# jan_ray2.net
KiCad netlist of a schematic drawn in EAGLE
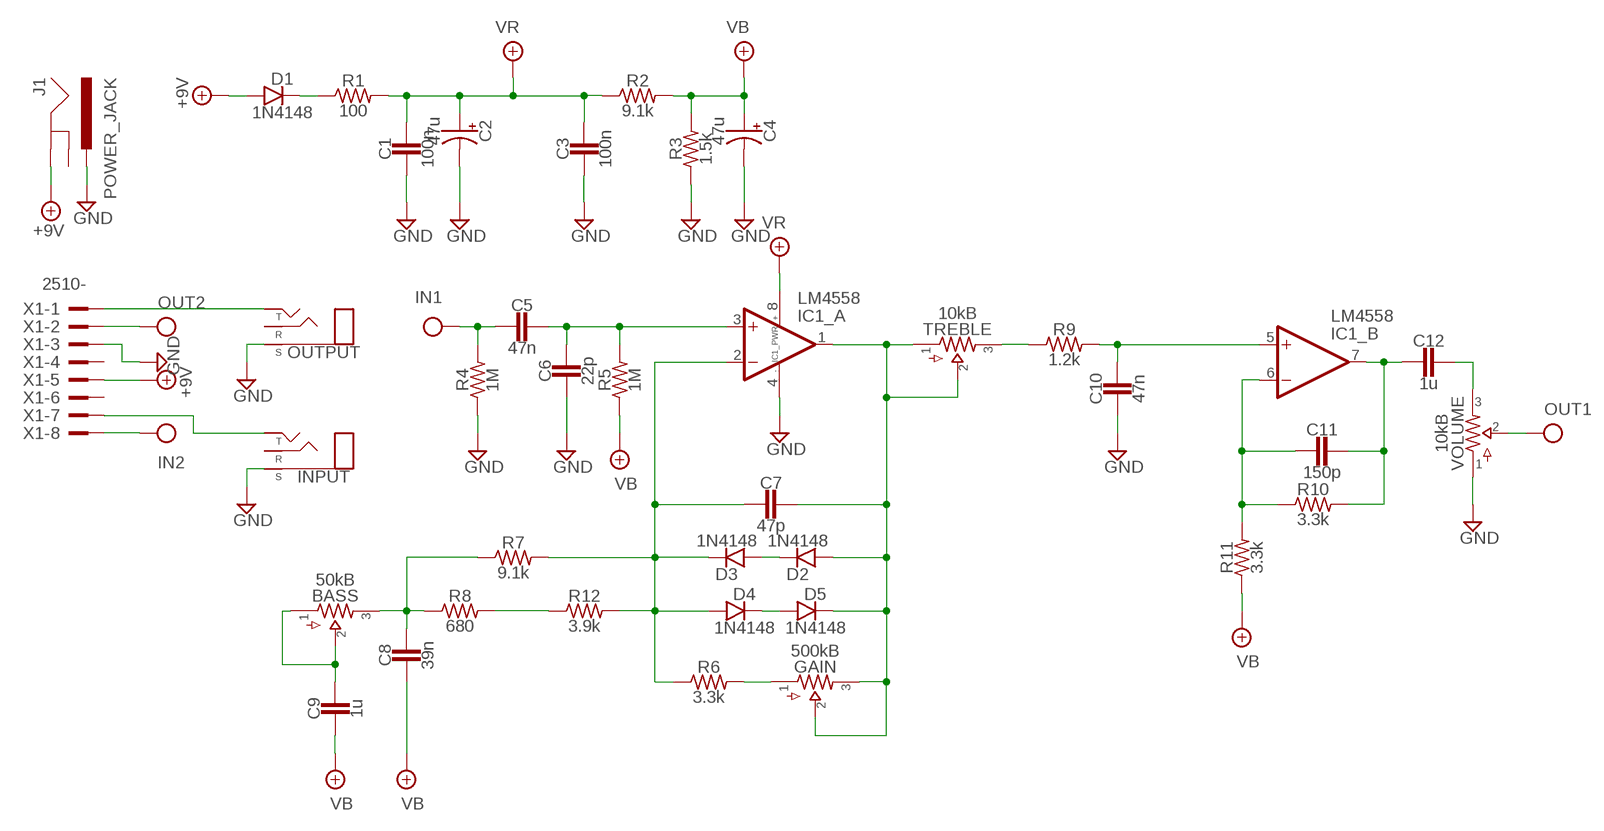
[diagram p0: schematic, sheet 1]

(export (version "E")
  (design (tool "Eeschema 10.0.6"))
  (components
    (comp (ref "BASS")
      (value "50kB")
      (footprint "eagle-import:16MM")
      (libsource (lib "eagle-import") (part "POTS16MM"))
    )
    (comp (ref "C1")
      (value "100n")
      (footprint "eagle-import:BOX_SMALL")
      (libsource (lib "eagle-import") (part "CER/FILMBOX.1"))
    )
    (comp (ref "C2")
      (value "47u")
      (footprint "eagle-import:050_020_1")
      (libsource (lib "eagle-import") (part "0501"))
    )
    (comp (ref "C3")
      (value "100n")
      (footprint "eagle-import:BOX_SMALL")
      (libsource (lib "eagle-import") (part "CER/FILMBOX.1"))
    )
    (comp (ref "C4")
      (value "47u")
      (footprint "eagle-import:050_020_1")
      (libsource (lib "eagle-import") (part "0501"))
    )
    (comp (ref "C5")
      (value "47n")
      (footprint "eagle-import:BOX_SMALL")
      (libsource (lib "eagle-import") (part "CER/FILMBOX.1"))
    )
    (comp (ref "C6")
      (value "22p")
      (footprint "eagle-import:050X030_025_2")
      (libsource (lib "eagle-import") (part "CER/FILM2"))
    )
    (comp (ref "C7")
      (value "47p")
      (footprint "eagle-import:050X030_025_2")
      (libsource (lib "eagle-import") (part "CER/FILM2"))
    )
    (comp (ref "C8")
      (value "39n")
      (footprint "eagle-import:BOX_SMALL")
      (libsource (lib "eagle-import") (part "CER/FILMBOX.1"))
    )
    (comp (ref "C9")
      (value "1u")
      (footprint "eagle-import:BOX_MED")
      (libsource (lib "eagle-import") (part "CER/FILMBOX.2"))
    )
    (comp (ref "C10")
      (value "47n")
      (footprint "eagle-import:BOX_SMALL")
      (libsource (lib "eagle-import") (part "CER/FILMBOX.1"))
    )
    (comp (ref "C11")
      (value "150p")
      (footprint "eagle-import:050X030_025_2")
      (libsource (lib "eagle-import") (part "CER/FILM2"))
    )
    (comp (ref "C12")
      (value "1u")
      (footprint "eagle-import:BOX_MED")
      (libsource (lib "eagle-import") (part "CER/FILMBOX.2"))
    )
    (comp (ref "D1")
      (value "1N4148")
      (footprint "eagle-import:DO35-2")
      (libsource (lib "eagle-import") (part "DO35.2"))
    )
    (comp (ref "D2")
      (value "1N4148")
      (footprint "eagle-import:DO35-2")
      (libsource (lib "eagle-import") (part "DO35.2"))
    )
    (comp (ref "D3")
      (value "1N4148")
      (footprint "eagle-import:DO35-2")
      (libsource (lib "eagle-import") (part "DO35.2"))
    )
    (comp (ref "D4")
      (value "1N4148")
      (footprint "eagle-import:DO35-2")
      (libsource (lib "eagle-import") (part "DO35.2"))
    )
    (comp (ref "D5")
      (value "1N4148")
      (footprint "eagle-import:DO35-2")
      (libsource (lib "eagle-import") (part "DO35.2"))
    )
    (comp (ref "GAIN")
      (value "500kB")
      (footprint "eagle-import:16MM")
      (libsource (lib "eagle-import") (part "POTS16MM"))
    )
    (comp (ref "IC1")
      (value "LM4558")
      (footprint "eagle-import:DIL08")
      (libsource (lib "eagle-import") (part "DUALTH"))
    )
    (comp (ref "INPUT")
      (value "STEREONMJ")
      (footprint "eagle-import:NMJ6HCD2")
      (libsource (lib "eagle-import") (part "STEREONMJ"))
    )
    (comp (ref "J1")
      (value "POWER_JACK")
      (footprint "eagle-import:POWER_JACK_PTH")
      (libsource (lib "eagle-import") (part "POWER_JACK"))
    )
    (comp (ref "OUTPUT")
      (value "STEREONMJ")
      (footprint "eagle-import:NMJ6HCD2")
      (libsource (lib "eagle-import") (part "STEREONMJ"))
    )
    (comp (ref "R1")
      (value "100")
      (footprint "eagle-import:R0207_3")
      (libsource (lib "eagle-import") (part "R_.3B"))
    )
    (comp (ref "R2")
      (value "9.1k")
      (footprint "eagle-import:R0207_3")
      (libsource (lib "eagle-import") (part "R_.3B"))
    )
    (comp (ref "R3")
      (value "1.5k")
      (footprint "eagle-import:R0207_3")
      (libsource (lib "eagle-import") (part "R_.3B"))
    )
    (comp (ref "R4")
      (value "1M")
      (footprint "eagle-import:R0207_3")
      (libsource (lib "eagle-import") (part "R_.3B"))
    )
    (comp (ref "R5")
      (value "1M")
      (footprint "eagle-import:R0207_3")
      (libsource (lib "eagle-import") (part "R_.3B"))
    )
    (comp (ref "R6")
      (value "3.3k")
      (footprint "eagle-import:R0207_3")
      (libsource (lib "eagle-import") (part "R_.3B"))
    )
    (comp (ref "R7")
      (value "9.1k")
      (footprint "eagle-import:R0207_3")
      (libsource (lib "eagle-import") (part "R_.3B"))
    )
    (comp (ref "R8")
      (value "680")
      (footprint "eagle-import:R0207_3")
      (libsource (lib "eagle-import") (part "R_.3B"))
    )
    (comp (ref "R9")
      (value "1.2k")
      (footprint "eagle-import:R0207_3")
      (libsource (lib "eagle-import") (part "R_.3B"))
    )
    (comp (ref "R10")
      (value "3.3k")
      (footprint "eagle-import:R0207_3")
      (libsource (lib "eagle-import") (part "R_.3B"))
    )
    (comp (ref "R11")
      (value "3.3k")
      (footprint "eagle-import:R0207_3")
      (libsource (lib "eagle-import") (part "R_.3B"))
    )
    (comp (ref "R12")
      (value "3.9k")
      (footprint "eagle-import:R0207_3")
      (libsource (lib "eagle-import") (part "R_.3B"))
    )
    (comp (ref "TREBLE")
      (value "10kB")
      (footprint "eagle-import:16MM")
      (libsource (lib "eagle-import") (part "POTS16MM"))
    )
    (comp (ref "VOLUME")
      (value "10kB")
      (footprint "eagle-import:16MM")
      (libsource (lib "eagle-import") (part "POTS16MM"))
    )
    (comp (ref "X1")
      (value "2510-")
      (footprint "eagle-import:PAK100_2500-10")
      (fields (field (name "MF") "3M") (field (name "MPN") "2510-6002UB"))
      (libsource (lib "eagle-import") (part "2510-"))
    )
  )
  (nets
    (net (code "1") (name "+9V") (class "Default")
      (node (ref "D1") (pin "A") (pinfunction "A_A") (pintype "passive"))
      (node (ref "J1") (pin "GND") (pinfunction "GND_GND") (pintype "bidirectional"))
      (node (ref "X1") (pin "5") (pinfunction "KL_5") (pintype "passive"))
    )
    (net (code "2") (name "GND") (class "Default")
      (node (ref "C1") (pin "2") (pinfunction "2_2") (pintype "passive"))
      (node (ref "C10") (pin "2") (pinfunction "2_2") (pintype "passive"))
      (node (ref "C2") (pin "-") (pinfunction "-_-") (pintype "passive"))
      (node (ref "C3") (pin "2") (pinfunction "2_2") (pintype "passive"))
      (node (ref "C4") (pin "-") (pinfunction "-_-") (pintype "passive"))
      (node (ref "C6") (pin "2") (pinfunction "2_2") (pintype "passive"))
      (node (ref "IC1") (pin "4") (pinfunction "V-_4") (pintype "power_in"))
      (node (ref "INPUT") (pin "S") (pinfunction "S_S") (pintype "passive"))
      (node (ref "J1") (pin "PWR") (pinfunction "PWR_PWR") (pintype "bidirectional"))
      (node (ref "OUTPUT") (pin "S") (pinfunction "S_S") (pintype "passive"))
      (node (ref "R3") (pin "1") (pinfunction "1_1") (pintype "passive"))
      (node (ref "R4") (pin "1") (pinfunction "1_1") (pintype "passive"))
      (node (ref "VOLUME") (pin "1") (pinfunction "1_1") (pintype "passive"))
      (node (ref "X1") (pin "3") (pinfunction "KL_3") (pintype "passive"))
    )
    (net (code "3") (name "IN") (class "Default")
      (node (ref "C5") (pin "2") (pinfunction "2_2") (pintype "passive"))
      (node (ref "R4") (pin "2") (pinfunction "2_2") (pintype "passive"))
      (node (ref "X1") (pin "8") (pinfunction "KL_8") (pintype "passive"))
    )
    (net (code "4") (name "Net-(BASS-Pad1)") (class "Default")
      (node (ref "BASS") (pin "1") (pinfunction "1_1") (pintype "passive"))
      (node (ref "BASS") (pin "2") (pinfunction "2_2") (pintype "passive"))
      (node (ref "C9") (pin "1") (pinfunction "1_1") (pintype "passive"))
    )
    (net (code "5") (name "Net-(BASS-Pad3)") (class "Default")
      (node (ref "BASS") (pin "3") (pinfunction "3_3") (pintype "passive"))
      (node (ref "C8") (pin "1") (pinfunction "1_1") (pintype "passive"))
      (node (ref "R7") (pin "1") (pinfunction "1_1") (pintype "passive"))
      (node (ref "R8") (pin "1") (pinfunction "1_1") (pintype "passive"))
    )
    (net (code "6") (name "Net-(C12-Pad1)") (class "Default")
      (node (ref "C12") (pin "1") (pinfunction "1_1") (pintype "passive"))
      (node (ref "VOLUME") (pin "3") (pinfunction "3_3") (pintype "passive"))
    )
    (net (code "7") (name "Net-(D1-PadC)") (class "Default")
      (node (ref "D1") (pin "C") (pinfunction "C_C") (pintype "passive"))
      (node (ref "R1") (pin "1") (pinfunction "1_1") (pintype "passive"))
    )
    (net (code "8") (name "Net-(D2-PadC)") (class "Default")
      (node (ref "D2") (pin "C") (pinfunction "C_C") (pintype "passive"))
      (node (ref "D3") (pin "A") (pinfunction "A_A") (pintype "passive"))
    )
    (net (code "9") (name "Net-(D4-PadC)") (class "Default")
      (node (ref "D4") (pin "C") (pinfunction "C_C") (pintype "passive"))
      (node (ref "D5") (pin "A") (pinfunction "A_A") (pintype "passive"))
    )
    (net (code "10") (name "Net-(GAIN-Pad1)") (class "Default")
      (node (ref "GAIN") (pin "1") (pinfunction "1_1") (pintype "passive"))
      (node (ref "R6") (pin "2") (pinfunction "2_2") (pintype "passive"))
    )
    (net (code "11") (name "Net-(IC1A-+IN)") (class "Default")
      (node (ref "C5") (pin "1") (pinfunction "1_1") (pintype "passive"))
      (node (ref "C6") (pin "1") (pinfunction "1_1") (pintype "passive"))
      (node (ref "IC1") (pin "3") (pinfunction "+IN_3") (pintype "input"))
      (node (ref "R5") (pin "2") (pinfunction "2_2") (pintype "passive"))
    )
    (net (code "12") (name "Net-(IC1A--IN)") (class "Default")
      (node (ref "C7") (pin "2") (pinfunction "2_2") (pintype "passive"))
      (node (ref "D3") (pin "C") (pinfunction "C_C") (pintype "passive"))
      (node (ref "D4") (pin "A") (pinfunction "A_A") (pintype "passive"))
      (node (ref "IC1") (pin "2") (pinfunction "-IN_2") (pintype "input"))
      (node (ref "R12") (pin "2") (pinfunction "2_2") (pintype "passive"))
      (node (ref "R6") (pin "1") (pinfunction "1_1") (pintype "passive"))
      (node (ref "R7") (pin "2") (pinfunction "2_2") (pintype "passive"))
    )
    (net (code "13") (name "Net-(IC1A-OUT)") (class "Default")
      (node (ref "C7") (pin "1") (pinfunction "1_1") (pintype "passive"))
      (node (ref "D2") (pin "A") (pinfunction "A_A") (pintype "passive"))
      (node (ref "D5") (pin "C") (pinfunction "C_C") (pintype "passive"))
      (node (ref "GAIN") (pin "2") (pinfunction "2_2") (pintype "passive"))
      (node (ref "GAIN") (pin "3") (pinfunction "3_3") (pintype "passive"))
      (node (ref "IC1") (pin "1") (pinfunction "OUT_1") (pintype "output"))
      (node (ref "TREBLE") (pin "1") (pinfunction "1_1") (pintype "passive"))
      (node (ref "TREBLE") (pin "2") (pinfunction "2_2") (pintype "passive"))
    )
    (net (code "14") (name "Net-(IC1B-+IN)") (class "Default")
      (node (ref "C10") (pin "1") (pinfunction "1_1") (pintype "passive"))
      (node (ref "IC1") (pin "5") (pinfunction "+IN_5") (pintype "input"))
      (node (ref "R9") (pin "2") (pinfunction "2_2") (pintype "passive"))
    )
    (net (code "15") (name "Net-(IC1B--IN)") (class "Default")
      (node (ref "C11") (pin "2") (pinfunction "2_2") (pintype "passive"))
      (node (ref "IC1") (pin "6") (pinfunction "-IN_6") (pintype "input"))
      (node (ref "R10") (pin "1") (pinfunction "1_1") (pintype "passive"))
      (node (ref "R11") (pin "2") (pinfunction "2_2") (pintype "passive"))
    )
    (net (code "16") (name "Net-(IC1B-OUT)") (class "Default")
      (node (ref "C11") (pin "1") (pinfunction "1_1") (pintype "passive"))
      (node (ref "C12") (pin "2") (pinfunction "2_2") (pintype "passive"))
      (node (ref "IC1") (pin "7") (pinfunction "OUT_7") (pintype "output"))
      (node (ref "R10") (pin "2") (pinfunction "2_2") (pintype "passive"))
    )
    (net (code "17") (name "Net-(R9-Pad1)") (class "Default")
      (node (ref "R9") (pin "1") (pinfunction "1_1") (pintype "passive"))
      (node (ref "TREBLE") (pin "3") (pinfunction "3_3") (pintype "passive"))
    )
    (net (code "18") (name "Net-(R12-Pad1)") (class "Default")
      (node (ref "R12") (pin "1") (pinfunction "1_1") (pintype "passive"))
      (node (ref "R8") (pin "2") (pinfunction "2_2") (pintype "passive"))
    )
    (net (code "19") (name "Net-(X1A-KL)") (class "Default")
      (node (ref "OUTPUT") (pin "T") (pinfunction "T_T") (pintype "passive"))
      (node (ref "X1") (pin "1") (pinfunction "KL_1") (pintype "passive"))
    )
    (net (code "20") (name "Net-(X1G-KL)") (class "Default")
      (node (ref "INPUT") (pin "T") (pinfunction "T_T") (pintype "passive"))
      (node (ref "X1") (pin "7") (pinfunction "KL_7") (pintype "passive"))
    )
    (net (code "21") (name "OUT") (class "Default")
      (node (ref "VOLUME") (pin "2") (pinfunction "2_2") (pintype "passive"))
      (node (ref "X1") (pin "2") (pinfunction "KL_2") (pintype "passive"))
    )
    (net (code "22") (name "VB") (class "Default")
      (node (ref "C4") (pin "+") (pinfunction "+_+") (pintype "passive"))
      (node (ref "C8") (pin "2") (pinfunction "2_2") (pintype "passive"))
      (node (ref "C9") (pin "2") (pinfunction "2_2") (pintype "passive"))
      (node (ref "R11") (pin "1") (pinfunction "1_1") (pintype "passive"))
      (node (ref "R2") (pin "2") (pinfunction "2_2") (pintype "passive"))
      (node (ref "R3") (pin "2") (pinfunction "2_2") (pintype "passive"))
      (node (ref "R5") (pin "1") (pinfunction "1_1") (pintype "passive"))
    )
    (net (code "23") (name "VR") (class "Default")
      (node (ref "C1") (pin "1") (pinfunction "1_1") (pintype "passive"))
      (node (ref "C2") (pin "+") (pinfunction "+_+") (pintype "passive"))
      (node (ref "C3") (pin "1") (pinfunction "1_1") (pintype "passive"))
      (node (ref "IC1") (pin "8") (pinfunction "V+_8") (pintype "power_in"))
      (node (ref "R1") (pin "2") (pinfunction "2_2") (pintype "passive"))
      (node (ref "R2") (pin "1") (pinfunction "1_1") (pintype "passive"))
    )
    (net (code "24") (name "unconnected-(INPUT-PadR)") (class "Default")
      (node (ref "INPUT") (pin "R") (pinfunction "R_R") (pintype "passive"))
    )
    (net (code "25") (name "unconnected-(J1-PadGNDBREAK)") (class "Default")
      (node (ref "J1") (pin "GNDBREAK") (pinfunction "GNDBREAK_GNDBREAK") (pintype "bidirectional"))
    )
    (net (code "26") (name "unconnected-(OUTPUT-PadR)") (class "Default")
      (node (ref "OUTPUT") (pin "R") (pinfunction "R_R") (pintype "passive"))
    )
    (net (code "27") (name "unconnected-(X1D-KL-Pad4)") (class "Default")
      (node (ref "X1") (pin "4") (pinfunction "KL_4") (pintype "passive"))
    )
    (net (code "28") (name "unconnected-(X1F-KL-Pad6)") (class "Default")
      (node (ref "X1") (pin "6") (pinfunction "KL_6") (pintype "passive"))
    )
  )
)
